# ESP32.net
KiCad netlist of a schematic drawn in Altium Designer
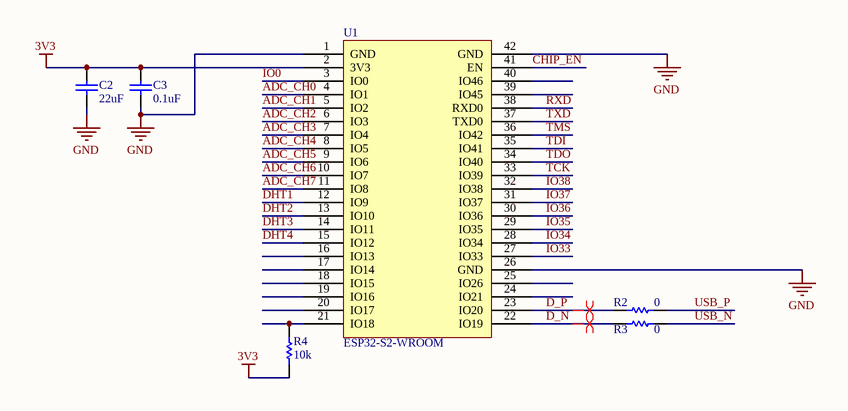
[diagram p0: ESP32.SchDoc]

(export (version "E")
  (design (tool "Eeschema 10.0.6"))
  (components
    (comp (ref "C2")
      (value "22uF")
      (footprint "C0805")
      (description "LMK212BJ226MG-T TAIYO YU DEN CERAMIC CAPACITOR 22U F 20% 10V X5R 0805 RoHS")
      (libsource (lib "CommunityVault") (part "SYM-3afbf396deb1e53c-1"))
    )
    (comp (ref "C3")
      (value "0.1uF")
      (footprint "0402C")
      (description "0402 0.1 uF 10 V ±10 % Tolerance X5R Surface Mount Multilayer Ceramic Capacitor")
      (fields (field (name "MANUFACTURER PART NUMBER") "GRM155R61A104KA01D"))
      (libsource (lib "CommunityVault") (part "CAP-NP-2"))
    )
    (comp (ref "R2")
      (value "0")
      (footprint "PCB-azzhouwj1h0sqqpj65ny-1")
      (description "RC Series 0402 0.063 W 0 Ohms Jumper Surface Mount Thick Film Chip Resistor")
      (libsource (lib "CommunityVault") (part "SYM-3abff0f8c341e578-4"))
    )
    (comp (ref "R3")
      (value "0")
      (footprint "PCB-azzhouwj1h0sqqpj65ny-1")
      (description "RC Series 0402 0.063 W 0 Ohms Jumper Surface Mount Thick Film Chip Resistor")
      (libsource (lib "CommunityVault") (part "SYM-3abff0f8c341e578-4"))
    )
    (comp (ref "R4")
      (value "10k")
      (footprint "PCB-urbe6pl2f36u5sj9z9e0-1")
      (description "Res, AEC-Q200, Thick Film, 10K, 5%, 0603")
      (fields (field (name "MANUFACTURER PART NUMBER") "CRGCQ0603J10K"))
      (libsource (lib "CommunityVault") (part "SYM-1974d512ef63c6b3-1"))
    )
    (comp (ref "U1")
      (value "ESP32-S2-WROOM")
      (footprint "PCBComponent_1")
      (description "SMD Module ESP32-S2-WROOM")
      (libsource (lib "CommunityVault") (part "SYM-dacd15a1cbe3050a-1"))
    )
  )
  (nets
    (net (code "1") (name "/ADC_CH0") (class "Default")
      (node (ref "U1") (pin "4") (pinfunction "IO1_4") (pintype "passive"))
    )
    (net (code "2") (name "/ADC_CH1") (class "Default")
      (node (ref "U1") (pin "5") (pinfunction "IO2_5") (pintype "passive"))
    )
    (net (code "3") (name "/ADC_CH2") (class "Default")
      (node (ref "U1") (pin "6") (pinfunction "IO3_6") (pintype "passive"))
    )
    (net (code "4") (name "/ADC_CH3") (class "Default")
      (node (ref "U1") (pin "7") (pinfunction "IO4_7") (pintype "passive"))
    )
    (net (code "5") (name "/ADC_CH4") (class "Default")
      (node (ref "U1") (pin "8") (pinfunction "IO5_8") (pintype "passive"))
    )
    (net (code "6") (name "/ADC_CH5") (class "Default")
      (node (ref "U1") (pin "9") (pinfunction "IO6_9") (pintype "passive"))
    )
    (net (code "7") (name "/ADC_CH6") (class "Default")
      (node (ref "U1") (pin "10") (pinfunction "IO7_10") (pintype "passive"))
    )
    (net (code "8") (name "/ADC_CH7") (class "Default")
      (node (ref "U1") (pin "11") (pinfunction "IO8_11") (pintype "passive"))
    )
    (net (code "9") (name "/CHIP_EN") (class "Default")
      (node (ref "U1") (pin "41") (pinfunction "EN_41") (pintype "passive"))
    )
    (net (code "10") (name "/DHT1") (class "Default")
      (node (ref "U1") (pin "12") (pinfunction "IO9_12") (pintype "passive"))
    )
    (net (code "11") (name "/DHT2") (class "Default")
      (node (ref "U1") (pin "13") (pinfunction "IO10_13") (pintype "passive"))
    )
    (net (code "12") (name "/DHT3") (class "Default")
      (node (ref "U1") (pin "14") (pinfunction "IO11_14") (pintype "passive"))
    )
    (net (code "13") (name "/DHT4") (class "Default")
      (node (ref "U1") (pin "15") (pinfunction "IO12_15") (pintype "passive"))
    )
    (net (code "14") (name "/D_N") (class "Default")
      (node (ref "R3") (pin "1") (pinfunction "1_1") (pintype "passive"))
      (node (ref "U1") (pin "22") (pinfunction "IO19_22") (pintype "passive"))
    )
    (net (code "15") (name "/D_P") (class "Default")
      (node (ref "R2") (pin "1") (pinfunction "1_1") (pintype "passive"))
      (node (ref "U1") (pin "23") (pinfunction "IO20_23") (pintype "passive"))
    )
    (net (code "16") (name "/IO0") (class "Default")
      (node (ref "U1") (pin "3") (pinfunction "IO0_3") (pintype "passive"))
    )
    (net (code "17") (name "/IO33") (class "Default")
      (node (ref "U1") (pin "27") (pinfunction "IO33_27") (pintype "passive"))
    )
    (net (code "18") (name "/IO34") (class "Default")
      (node (ref "U1") (pin "28") (pinfunction "IO34_28") (pintype "passive"))
    )
    (net (code "19") (name "/IO35") (class "Default")
      (node (ref "U1") (pin "29") (pinfunction "IO35_29") (pintype "passive"))
    )
    (net (code "20") (name "/IO36") (class "Default")
      (node (ref "U1") (pin "30") (pinfunction "IO36_30") (pintype "passive"))
    )
    (net (code "21") (name "/IO37") (class "Default")
      (node (ref "U1") (pin "31") (pinfunction "IO37_31") (pintype "passive"))
    )
    (net (code "22") (name "/IO38") (class "Default")
      (node (ref "U1") (pin "32") (pinfunction "IO38_32") (pintype "passive"))
    )
    (net (code "23") (name "/RXD") (class "Default")
      (node (ref "U1") (pin "38") (pinfunction "RXD0_38") (pintype "passive"))
    )
    (net (code "24") (name "/TCK") (class "Default")
      (node (ref "U1") (pin "33") (pinfunction "IO39_33") (pintype "passive"))
    )
    (net (code "25") (name "/TDI") (class "Default")
      (node (ref "U1") (pin "35") (pinfunction "IO41_35") (pintype "passive"))
    )
    (net (code "26") (name "/TDO") (class "Default")
      (node (ref "U1") (pin "34") (pinfunction "IO40_34") (pintype "passive"))
    )
    (net (code "27") (name "/TMS") (class "Default")
      (node (ref "U1") (pin "36") (pinfunction "IO42_36") (pintype "passive"))
    )
    (net (code "28") (name "/TXD") (class "Default")
      (node (ref "U1") (pin "37") (pinfunction "TXD0_37") (pintype "passive"))
    )
    (net (code "29") (name "/USB_N") (class "Default")
      (node (ref "R3") (pin "2") (pinfunction "2_2") (pintype "passive"))
    )
    (net (code "30") (name "/USB_P") (class "Default")
      (node (ref "R2") (pin "2") (pinfunction "2_2") (pintype "passive"))
    )
    (net (code "31") (name "3V3") (class "Default")
      (node (ref "C2") (pin "2") (pinfunction "2_2") (pintype "passive"))
      (node (ref "C3") (pin "1") (pinfunction "1_1") (pintype "passive"))
      (node (ref "R4") (pin "2") (pinfunction "2_2") (pintype "passive"))
      (node (ref "U1") (pin "2") (pinfunction "3V3_2") (pintype "passive"))
    )
    (net (code "32") (name "GND") (class "Default")
      (node (ref "C2") (pin "1") (pinfunction "1_1") (pintype "passive"))
      (node (ref "C3") (pin "2") (pinfunction "2_2") (pintype "passive"))
      (node (ref "U1") (pin "1") (pinfunction "GND_1") (pintype "passive"))
      (node (ref "U1") (pin "26") (pinfunction "GND_26") (pintype "passive"))
      (node (ref "U1") (pin "42") (pinfunction "GND_42") (pintype "passive"))
    )
    (net (code "33") (name "Net-(U1-IO18)") (class "Default")
      (node (ref "R4") (pin "1") (pinfunction "1_1") (pintype "passive"))
      (node (ref "U1") (pin "21") (pinfunction "IO18_21") (pintype "passive"))
    )
    (net (code "34") (name "unconnected-(U1-IO13-Pad16)") (class "Default")
      (node (ref "U1") (pin "16") (pinfunction "IO13_16") (pintype "passive"))
    )
    (net (code "35") (name "unconnected-(U1-IO14-Pad17)") (class "Default")
      (node (ref "U1") (pin "17") (pinfunction "IO14_17") (pintype "passive"))
    )
    (net (code "36") (name "unconnected-(U1-IO15-Pad18)") (class "Default")
      (node (ref "U1") (pin "18") (pinfunction "IO15_18") (pintype "passive"))
    )
    (net (code "37") (name "unconnected-(U1-IO16-Pad19)") (class "Default")
      (node (ref "U1") (pin "19") (pinfunction "IO16_19") (pintype "passive"))
    )
    (net (code "38") (name "unconnected-(U1-IO17-Pad20)") (class "Default")
      (node (ref "U1") (pin "20") (pinfunction "IO17_20") (pintype "passive"))
    )
    (net (code "39") (name "unconnected-(U1-IO21-Pad24)") (class "Default")
      (node (ref "U1") (pin "24") (pinfunction "IO21_24") (pintype "passive"))
    )
    (net (code "40") (name "unconnected-(U1-IO26-Pad25)") (class "Default")
      (node (ref "U1") (pin "25") (pinfunction "IO26_25") (pintype "passive"))
    )
    (net (code "41") (name "unconnected-(U1-IO45-Pad39)") (class "Default")
      (node (ref "U1") (pin "39") (pinfunction "IO45_39") (pintype "passive"))
    )
    (net (code "42") (name "unconnected-(U1-IO46-Pad40)") (class "Default")
      (node (ref "U1") (pin "40") (pinfunction "IO46_40") (pintype "passive"))
    )
  )
)
